# 03-CPU_Core.net
KiCad netlist of a schematic drawn in Altium Designer
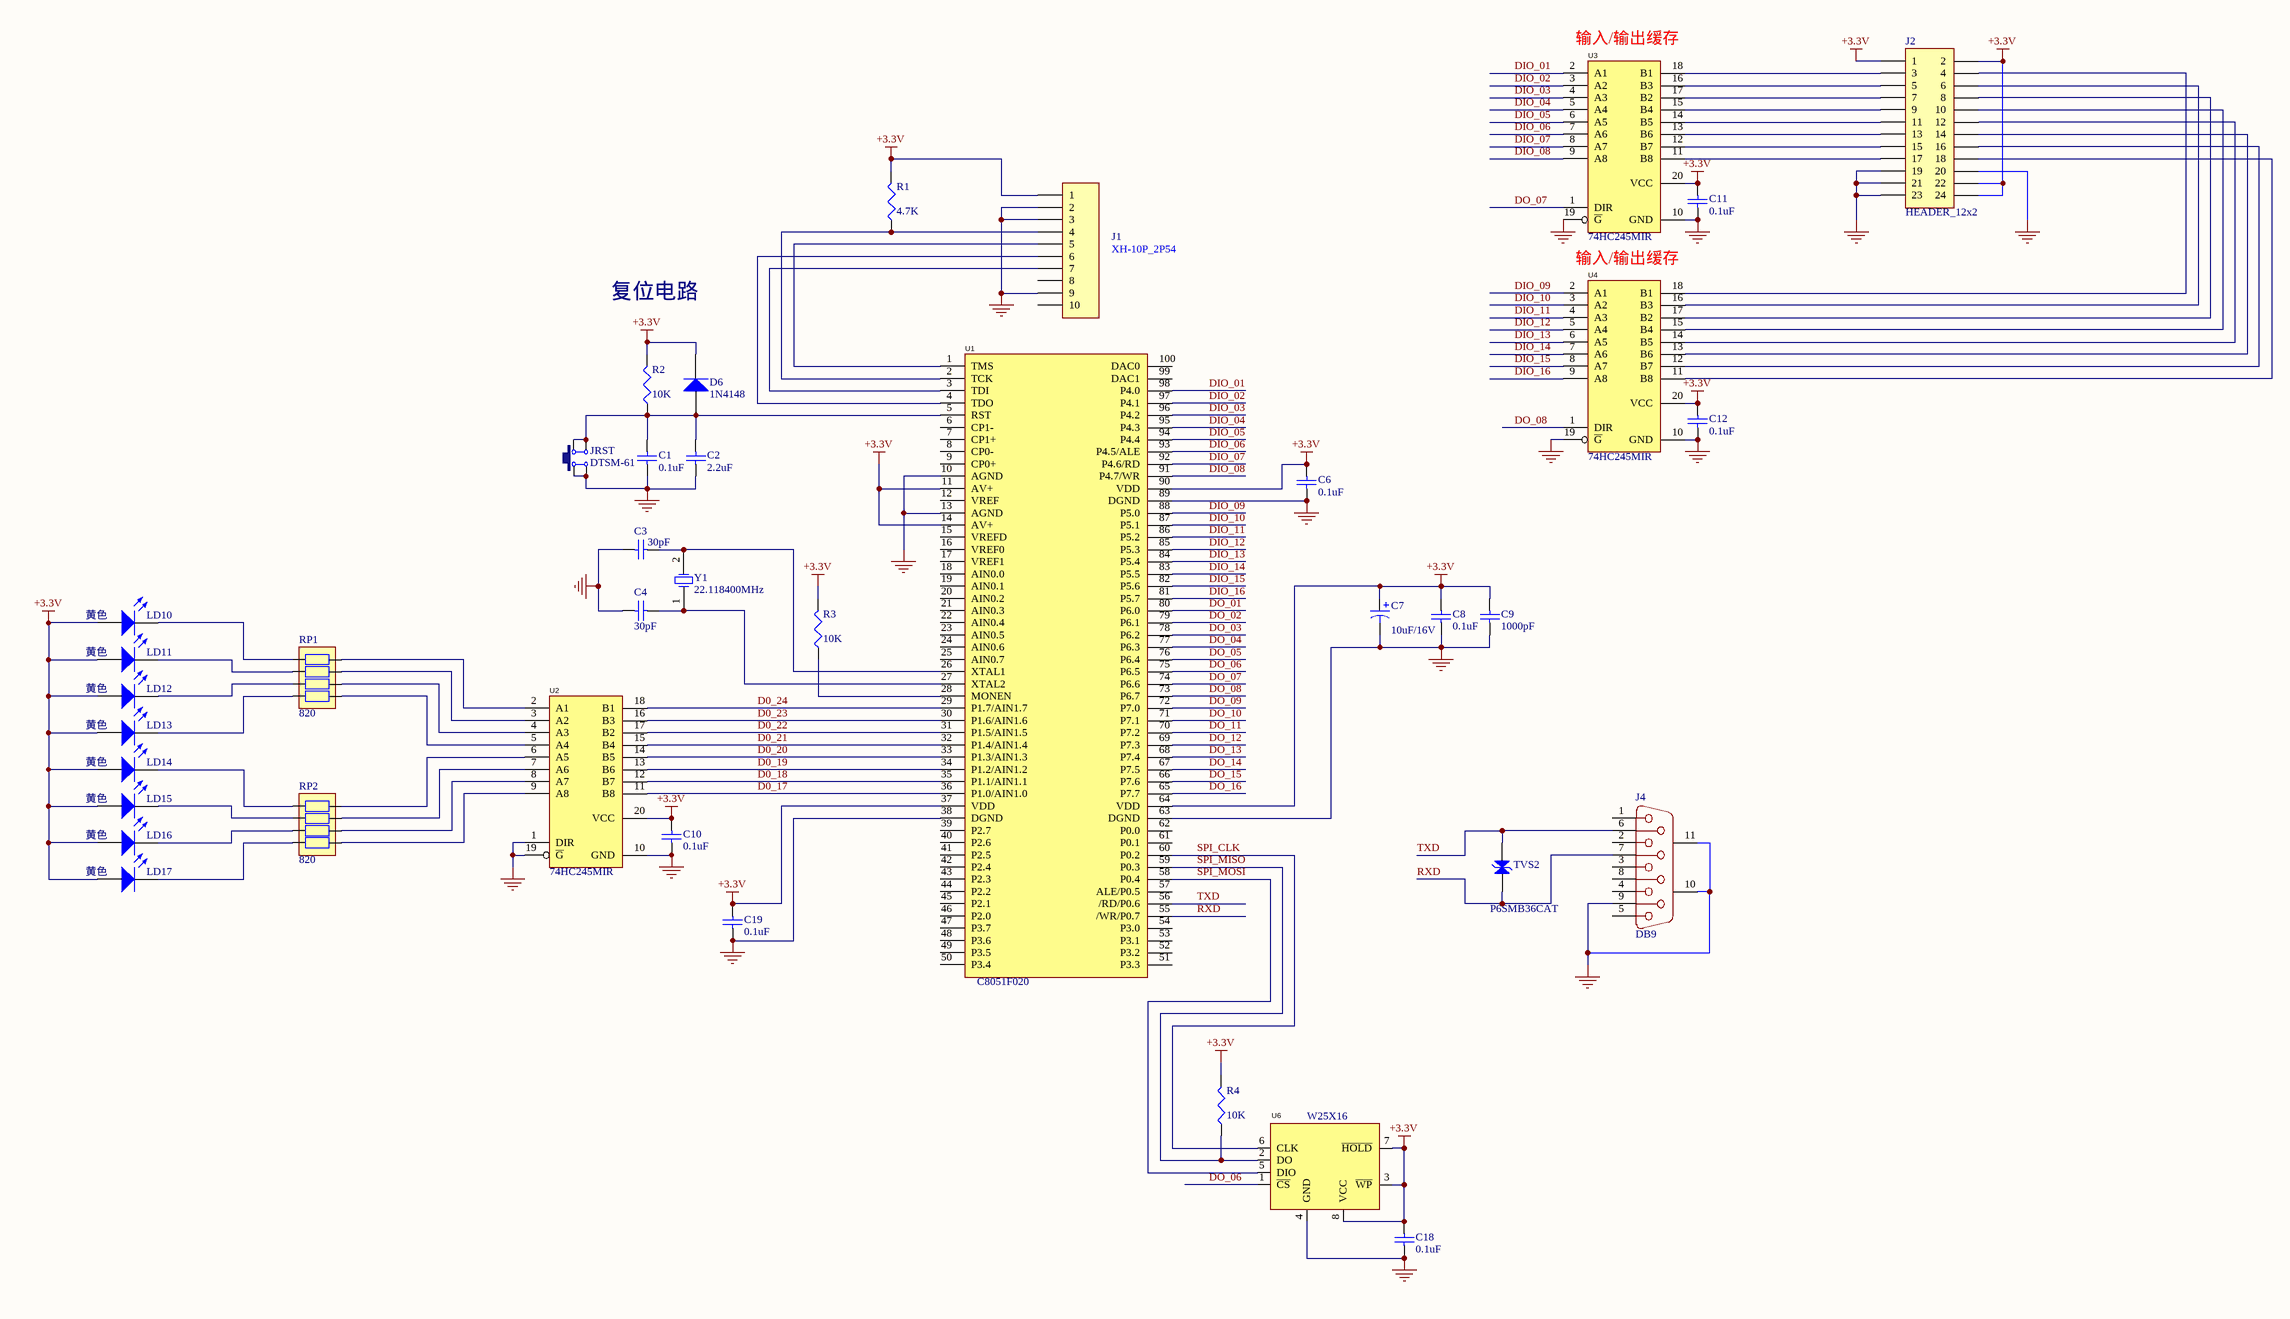
[diagram p0: 03-CPU Core.SchDoc]

(export (version "E")
  (design (tool "Eeschema 10.0.6"))
  (components
    (comp (ref "C1")
      (value "0.1uF")
      (footprint "C0805")
      (description "Capacitor")
      (fields (field (name "Comment") "Cap") (field (name "PUBLISHER") "Altium Limited"))
      (libsource (lib "Miscellaneous Devices") (part "Cap"))
    )
    (comp (ref "C2")
      (value "2.2uF")
      (footprint "C0805")
      (description "Capacitor")
      (fields (field (name "Comment") "Cap") (field (name "PUBLISHER") "Altium Limited"))
      (libsource (lib "Miscellaneous Devices") (part "Cap"))
    )
    (comp (ref "C3")
      (value "30pF")
      (footprint "C0805")
      (description "Capacitor")
      (fields (field (name "Comment") "Cap") (field (name "PUBLISHER") "Altium Limited"))
      (libsource (lib "Miscellaneous Devices") (part "Cap"))
    )
    (comp (ref "C4")
      (value "30pF")
      (footprint "C0805")
      (description "Capacitor")
      (fields (field (name "Comment") "Cap") (field (name "PUBLISHER") "Altium Limited"))
      (libsource (lib "Miscellaneous Devices") (part "Cap"))
    )
    (comp (ref "C6")
      (value "0.1uF")
      (footprint "C0805")
      (description "Capacitor")
      (fields (field (name "Comment") "Cap") (field (name "PUBLISHER") "Altium Limited"))
      (libsource (lib "Miscellaneous Devices") (part "Cap"))
    )
    (comp (ref "C7")
      (value "10uF/16V")
      (footprint "C3216")
      (description "Polarized Capacitor (Radial)")
      (fields (field (name "Comment") "Cap Pol1") (field (name "PUBLISHER") "Altium Limited"))
      (libsource (lib "Miscellaneous Devices") (part "Cap Pol1"))
    )
    (comp (ref "C8")
      (value "0.1uF")
      (footprint "C0805")
      (description "Capacitor")
      (fields (field (name "Comment") "Cap") (field (name "PUBLISHER") "Altium Limited"))
      (libsource (lib "Miscellaneous Devices") (part "Cap"))
    )
    (comp (ref "C9")
      (value "1000pF")
      (footprint "C0805")
      (description "Capacitor")
      (fields (field (name "Comment") "Cap") (field (name "PUBLISHER") "Altium Limited"))
      (libsource (lib "Miscellaneous Devices") (part "Cap"))
    )
    (comp (ref "C10")
      (value "0.1uF")
      (footprint "C0805")
      (description "Capacitor")
      (fields (field (name "Comment") "Cap") (field (name "PUBLISHER") "Altium Limited"))
      (libsource (lib "Miscellaneous Devices") (part "Cap"))
    )
    (comp (ref "C11")
      (value "0.1uF")
      (footprint "C0805")
      (description "Capacitor")
      (fields (field (name "Comment") "Cap") (field (name "PUBLISHER") "Altium Limited"))
      (libsource (lib "Miscellaneous Devices") (part "Cap"))
    )
    (comp (ref "C12")
      (value "0.1uF")
      (footprint "C0805")
      (description "Capacitor")
      (fields (field (name "Comment") "Cap") (field (name "PUBLISHER") "Altium Limited"))
      (libsource (lib "Miscellaneous Devices") (part "Cap"))
    )
    (comp (ref "C18")
      (value "0.1uF")
      (footprint "C0805")
      (description "Capacitor")
      (fields (field (name "Comment") "Cap") (field (name "PUBLISHER") "Altium Limited"))
      (libsource (lib "Miscellaneous Devices") (part "Cap"))
    )
    (comp (ref "C19")
      (value "0.1uF")
      (footprint "C0805")
      (description "Capacitor")
      (fields (field (name "Comment") "Cap") (field (name "PUBLISHER") "Altium Limited"))
      (libsource (lib "Miscellaneous Devices") (part "Cap"))
    )
    (comp (ref "D6")
      (value "1N4148")
      (footprint "FR107W")
      (description "Default Diode")
      (fields (field (name "PUBLISHER") "Altium Limited"))
      (libsource (lib "Miscellaneous Devices") (part "Diode"))
    )
    (comp (ref "J1")
      (value "XH-10P_2P54")
      (footprint "XH-10P_2P54")
      (description "Header, 10-Pin")
      (fields (field (name "PUBLISHER") "Altium Limited"))
      (libsource (lib "Miscellaneous Connectors") (part "Header 10"))
    )
    (comp (ref "J2")
      (value "HEADER_12x2")
      (footprint "HEADER_12x2")
      (description "Header, 12-Pin, Dual row")
      (fields (field (name "PUBLISHER") "Altium Limited"))
      (libsource (lib "Miscellaneous Connectors") (part "Header 12X2"))
    )
    (comp (ref "J4") (value "DB9") (footprint "DB9") (libsource (lib "SCHLIB") (part "DB9")))
    (comp (ref "JRST") (value "DTSM-61") (footprint "DISM-61") (libsource (lib "SCHLIB") (part "DTSM-61")))
    (comp (ref "LD10")
      (value "黄色")
      (footprint "LED0805")
      (description "Typical INFRARED GaAs LED")
      (fields (field (name "PUBLISHER") "Altium Limited"))
      (libsource (lib "Miscellaneous Devices") (part "LED0"))
    )
    (comp (ref "LD11")
      (value "黄色")
      (footprint "LED0805")
      (description "Typical INFRARED GaAs LED")
      (fields (field (name "PUBLISHER") "Altium Limited"))
      (libsource (lib "Miscellaneous Devices") (part "LED0"))
    )
    (comp (ref "LD12")
      (value "黄色")
      (footprint "LED0805")
      (description "Typical INFRARED GaAs LED")
      (fields (field (name "PUBLISHER") "Altium Limited"))
      (libsource (lib "Miscellaneous Devices") (part "LED0"))
    )
    (comp (ref "LD13")
      (value "黄色")
      (footprint "LED0805")
      (description "Typical INFRARED GaAs LED")
      (fields (field (name "PUBLISHER") "Altium Limited"))
      (libsource (lib "Miscellaneous Devices") (part "LED0"))
    )
    (comp (ref "LD14")
      (value "黄色")
      (footprint "LED0805")
      (description "Typical INFRARED GaAs LED")
      (fields (field (name "PUBLISHER") "Altium Limited"))
      (libsource (lib "Miscellaneous Devices") (part "LED0"))
    )
    (comp (ref "LD15")
      (value "黄色")
      (footprint "LED0805")
      (description "Typical INFRARED GaAs LED")
      (fields (field (name "PUBLISHER") "Altium Limited"))
      (libsource (lib "Miscellaneous Devices") (part "LED0"))
    )
    (comp (ref "LD16")
      (value "黄色")
      (footprint "LED0805")
      (description "Typical INFRARED GaAs LED")
      (fields (field (name "PUBLISHER") "Altium Limited"))
      (libsource (lib "Miscellaneous Devices") (part "LED0"))
    )
    (comp (ref "LD17")
      (value "黄色")
      (footprint "LED0805")
      (description "Typical INFRARED GaAs LED")
      (fields (field (name "PUBLISHER") "Altium Limited"))
      (libsource (lib "Miscellaneous Devices") (part "LED0"))
    )
    (comp (ref "R1")
      (value "4.7K")
      (footprint "R0805")
      (description "Resistor")
      (fields (field (name "Comment") "Res3") (field (name "PUBLISHER") "Altium Limited"))
      (libsource (lib "Miscellaneous Devices") (part "Res3"))
    )
    (comp (ref "R2")
      (value "10K")
      (footprint "R0805")
      (description "Resistor")
      (fields (field (name "Comment") "Res3") (field (name "PUBLISHER") "Altium Limited"))
      (libsource (lib "Miscellaneous Devices") (part "Res3"))
    )
    (comp (ref "R3")
      (value "10K")
      (footprint "R0805")
      (description "Resistor")
      (fields (field (name "Comment") "Res3") (field (name "PUBLISHER") "Altium Limited"))
      (libsource (lib "Miscellaneous Devices") (part "Res3"))
    )
    (comp (ref "R4")
      (value "10K")
      (footprint "R0805")
      (description "Resistor")
      (fields (field (name "Comment") "Res3") (field (name "PUBLISHER") "Altium Limited"))
      (libsource (lib "Miscellaneous Devices") (part "Res3"))
    )
    (comp (ref "RP1") (value "820") (footprint "RP") (libsource (lib "SCHLIB") (part "RP 820")))
    (comp (ref "RP2") (value "820") (footprint "RP") (libsource (lib "SCHLIB") (part "RP 820")))
    (comp (ref "TVS2") (value "P6SMB36CAT") (footprint "SMD") (libsource (lib "SCHLIB") (part "SMD")))
    (comp (ref "U1")
      (value "C8051F020")
      (footprint "TQFP-100")
      (fields
        (field (name "MANUFACTURER") "SKYWORKS/SILICON LABS(芯科)")
        (field (name "MANUFACTURER PART") "C8051F020-GQR")
      )
      (libsource (lib "C8051F020") (part "C8051F020"))
    )
    (comp (ref "U2")
      (value "74HC245MIR")
      (footprint "SSOP-20")
      (fields (field (name "MANUFACTURER") "Nexperia(安世)") (field (name "MANUFACTURER PART") "74HC245PW,118"))
      (libsource (lib "C8051F020") (part "74HC245MIR"))
    )
    (comp (ref "U3")
      (value "74HC245MIR")
      (footprint "SSOP-20")
      (fields (field (name "MANUFACTURER") "Nexperia(安世)") (field (name "MANUFACTURER PART") "74HC245PW,118"))
      (libsource (lib "C8051F020") (part "74HC245MIR"))
    )
    (comp (ref "U4")
      (value "74HC245MIR")
      (footprint "SSOP-20")
      (fields (field (name "MANUFACTURER") "Nexperia(安世)") (field (name "MANUFACTURER PART") "74HC245PW,118"))
      (libsource (lib "C8051F020") (part "74HC245MIR"))
    )
    (comp (ref "U6")
      (value "W25X16")
      (footprint "SOIC-8")
      (fields (field (name "MANUFACTURER") "WINBOND(华邦)") (field (name "MANUFACTURER PART") "W25X16VSSIG"))
      (libsource (lib "C8051F020") (part "W25X16"))
    )
    (comp (ref "Y1")
      (value "22.118400MHz")
      (footprint "HC-49")
      (description "Crystal Oscillator")
      (fields (field (name "PUBLISHER") "Altium Limited"))
      (libsource (lib "Miscellaneous Devices") (part "XTAL"))
    )
  )
  (nets
    (net (code "1") (name "+3.3V") (class "Default")
      (node (ref "C10") (pin "2") (pinfunction "2_2") (pintype "passive"))
      (node (ref "C11") (pin "2") (pinfunction "2_2") (pintype "passive"))
      (node (ref "C12") (pin "2") (pinfunction "2_2") (pintype "passive"))
      (node (ref "C18") (pin "2") (pinfunction "2_2") (pintype "passive"))
      (node (ref "C19") (pin "2") (pinfunction "2_2") (pintype "passive"))
      (node (ref "C6") (pin "2") (pinfunction "2_2") (pintype "passive"))
      (node (ref "C7") (pin "1") (pinfunction "1_1") (pintype "passive"))
      (node (ref "C8") (pin "2") (pinfunction "2_2") (pintype "passive"))
      (node (ref "C9") (pin "2") (pinfunction "2_2") (pintype "passive"))
      (node (ref "D6") (pin "2") (pinfunction "K_2") (pintype "passive"))
      (node (ref "J1") (pin "1") (pinfunction "1_1") (pintype "passive"))
      (node (ref "J2") (pin "1") (pinfunction "1_1") (pintype "passive"))
      (node (ref "J2") (pin "2") (pinfunction "2_2") (pintype "passive"))
      (node (ref "J2") (pin "22") (pinfunction "22_22") (pintype "passive"))
      (node (ref "J2") (pin "24") (pinfunction "24_24") (pintype "passive"))
      (node (ref "LD10") (pin "1") (pinfunction "A_1") (pintype "passive"))
      (node (ref "LD11") (pin "1") (pinfunction "A_1") (pintype "passive"))
      (node (ref "LD12") (pin "1") (pinfunction "A_1") (pintype "passive"))
      (node (ref "LD13") (pin "1") (pinfunction "A_1") (pintype "passive"))
      (node (ref "LD14") (pin "1") (pinfunction "A_1") (pintype "passive"))
      (node (ref "LD15") (pin "1") (pinfunction "A_1") (pintype "passive"))
      (node (ref "LD16") (pin "1") (pinfunction "A_1") (pintype "passive"))
      (node (ref "LD17") (pin "1") (pinfunction "A_1") (pintype "passive"))
      (node (ref "R1") (pin "2") (pinfunction "2_2") (pintype "passive"))
      (node (ref "R2") (pin "2") (pinfunction "2_2") (pintype "passive"))
      (node (ref "R3") (pin "2") (pinfunction "2_2") (pintype "passive"))
      (node (ref "R4") (pin "2") (pinfunction "2_2") (pintype "passive"))
      (node (ref "U1") (pin "11") (pinfunction "AV+_11") (pintype "passive"))
      (node (ref "U1") (pin "14") (pinfunction "AV+_14") (pintype "passive"))
      (node (ref "U1") (pin "37") (pinfunction "VDD_37") (pintype "passive"))
      (node (ref "U1") (pin "64") (pinfunction "VDD_64") (pintype "passive"))
      (node (ref "U1") (pin "90") (pinfunction "VDD_90") (pintype "passive"))
      (node (ref "U2") (pin "20") (pinfunction "VCC_20") (pintype "passive"))
      (node (ref "U3") (pin "20") (pinfunction "VCC_20") (pintype "passive"))
      (node (ref "U4") (pin "20") (pinfunction "VCC_20") (pintype "passive"))
      (node (ref "U6") (pin "3") (pinfunction "~{WP}_3") (pintype "passive"))
      (node (ref "U6") (pin "7") (pinfunction "~{HOLD}_7") (pintype "passive"))
      (node (ref "U6") (pin "8") (pinfunction "VCC_8") (pintype "passive"))
    )
    (net (code "2") (name "/D0_17") (class "Default")
      (node (ref "U1") (pin "36") (pinfunction "P1.0/AIN1.0_36") (pintype "passive"))
      (node (ref "U2") (pin "11") (pinfunction "B8_11") (pintype "passive"))
    )
    (net (code "3") (name "/D0_18") (class "Default")
      (node (ref "U1") (pin "35") (pinfunction "P1.1/AIN1.1_35") (pintype "passive"))
      (node (ref "U2") (pin "12") (pinfunction "B7_12") (pintype "passive"))
    )
    (net (code "4") (name "/D0_19") (class "Default")
      (node (ref "U1") (pin "34") (pinfunction "P1.2/AIN1.2_34") (pintype "passive"))
      (node (ref "U2") (pin "13") (pinfunction "B6_13") (pintype "passive"))
    )
    (net (code "5") (name "/D0_20") (class "Default")
      (node (ref "U1") (pin "33") (pinfunction "P1.3/AIN1.3_33") (pintype "passive"))
      (node (ref "U2") (pin "14") (pinfunction "B5_14") (pintype "passive"))
    )
    (net (code "6") (name "/D0_21") (class "Default")
      (node (ref "U1") (pin "32") (pinfunction "P1.4/AIN1.4_32") (pintype "passive"))
      (node (ref "U2") (pin "15") (pinfunction "B4_15") (pintype "passive"))
    )
    (net (code "7") (name "/D0_22") (class "Default")
      (node (ref "U1") (pin "31") (pinfunction "P1.5/AIN1.5_31") (pintype "passive"))
      (node (ref "U2") (pin "17") (pinfunction "B2_17") (pintype "passive"))
    )
    (net (code "8") (name "/D0_23") (class "Default")
      (node (ref "U1") (pin "30") (pinfunction "P1.6/AIN1.6_30") (pintype "passive"))
      (node (ref "U2") (pin "16") (pinfunction "B3_16") (pintype "passive"))
    )
    (net (code "9") (name "/D0_24") (class "Default")
      (node (ref "U1") (pin "29") (pinfunction "P1.7/AIN1.7_29") (pintype "passive"))
      (node (ref "U2") (pin "18") (pinfunction "B1_18") (pintype "passive"))
    )
    (net (code "10") (name "/DIO_01") (class "Default")
      (node (ref "U1") (pin "98") (pinfunction "P4.0_98") (pintype "passive"))
      (node (ref "U3") (pin "2") (pinfunction "A1_2") (pintype "passive"))
    )
    (net (code "11") (name "/DIO_02") (class "Default")
      (node (ref "U1") (pin "97") (pinfunction "P4.1_97") (pintype "passive"))
      (node (ref "U3") (pin "3") (pinfunction "A2_3") (pintype "passive"))
    )
    (net (code "12") (name "/DIO_03") (class "Default")
      (node (ref "U1") (pin "96") (pinfunction "P4.2_96") (pintype "passive"))
      (node (ref "U3") (pin "4") (pinfunction "A3_4") (pintype "passive"))
    )
    (net (code "13") (name "/DIO_04") (class "Default")
      (node (ref "U1") (pin "95") (pinfunction "P4.3_95") (pintype "passive"))
      (node (ref "U3") (pin "5") (pinfunction "A4_5") (pintype "passive"))
    )
    (net (code "14") (name "/DIO_05") (class "Default")
      (node (ref "U1") (pin "94") (pinfunction "P4.4_94") (pintype "passive"))
      (node (ref "U3") (pin "6") (pinfunction "A5_6") (pintype "passive"))
    )
    (net (code "15") (name "/DIO_06") (class "Default")
      (node (ref "U1") (pin "93") (pinfunction "P4.5/ALE_93") (pintype "passive"))
      (node (ref "U3") (pin "7") (pinfunction "A6_7") (pintype "passive"))
    )
    (net (code "16") (name "/DIO_07") (class "Default")
      (node (ref "U1") (pin "92") (pinfunction "P4.6/RD_92") (pintype "passive"))
      (node (ref "U3") (pin "8") (pinfunction "A7_8") (pintype "passive"))
    )
    (net (code "17") (name "/DIO_08") (class "Default")
      (node (ref "U1") (pin "91") (pinfunction "P4.7/WR_91") (pintype "passive"))
      (node (ref "U3") (pin "9") (pinfunction "A8_9") (pintype "passive"))
    )
    (net (code "18") (name "/DIO_09") (class "Default")
      (node (ref "U1") (pin "88") (pinfunction "P5.0_88") (pintype "passive"))
      (node (ref "U4") (pin "2") (pinfunction "A1_2") (pintype "passive"))
    )
    (net (code "19") (name "/DIO_10") (class "Default")
      (node (ref "U1") (pin "87") (pinfunction "P5.1_87") (pintype "passive"))
      (node (ref "U4") (pin "3") (pinfunction "A2_3") (pintype "passive"))
    )
    (net (code "20") (name "/DIO_11") (class "Default")
      (node (ref "U1") (pin "86") (pinfunction "P5.2_86") (pintype "passive"))
      (node (ref "U4") (pin "4") (pinfunction "A3_4") (pintype "passive"))
    )
    (net (code "21") (name "/DIO_12") (class "Default")
      (node (ref "U1") (pin "85") (pinfunction "P5.3_85") (pintype "passive"))
      (node (ref "U4") (pin "5") (pinfunction "A4_5") (pintype "passive"))
    )
    (net (code "22") (name "/DIO_13") (class "Default")
      (node (ref "U1") (pin "84") (pinfunction "P5.4_84") (pintype "passive"))
      (node (ref "U4") (pin "6") (pinfunction "A5_6") (pintype "passive"))
    )
    (net (code "23") (name "/DIO_14") (class "Default")
      (node (ref "U1") (pin "83") (pinfunction "P5.5_83") (pintype "passive"))
      (node (ref "U4") (pin "7") (pinfunction "A6_7") (pintype "passive"))
    )
    (net (code "24") (name "/DIO_15") (class "Default")
      (node (ref "U1") (pin "82") (pinfunction "P5.6_82") (pintype "passive"))
      (node (ref "U4") (pin "8") (pinfunction "A7_8") (pintype "passive"))
    )
    (net (code "25") (name "/DIO_16") (class "Default")
      (node (ref "U1") (pin "81") (pinfunction "P5.7_81") (pintype "passive"))
      (node (ref "U4") (pin "9") (pinfunction "A8_9") (pintype "passive"))
    )
    (net (code "26") (name "/DO_01") (class "Default")
      (node (ref "U1") (pin "80") (pinfunction "P6.0_80") (pintype "passive"))
    )
    (net (code "27") (name "/DO_02") (class "Default")
      (node (ref "U1") (pin "79") (pinfunction "P6.1_79") (pintype "passive"))
    )
    (net (code "28") (name "/DO_03") (class "Default")
      (node (ref "U1") (pin "78") (pinfunction "P6.2_78") (pintype "passive"))
    )
    (net (code "29") (name "/DO_04") (class "Default")
      (node (ref "U1") (pin "77") (pinfunction "P6.3_77") (pintype "passive"))
    )
    (net (code "30") (name "/DO_05") (class "Default")
      (node (ref "U1") (pin "76") (pinfunction "P6.4_76") (pintype "passive"))
    )
    (net (code "31") (name "/DO_06") (class "Default")
      (node (ref "U1") (pin "75") (pinfunction "P6.5_75") (pintype "passive"))
      (node (ref "U6") (pin "1") (pinfunction "~{CS}_1") (pintype "passive"))
    )
    (net (code "32") (name "/DO_07") (class "Default")
      (node (ref "U1") (pin "74") (pinfunction "P6.6_74") (pintype "passive"))
      (node (ref "U3") (pin "1") (pinfunction "DIR_1") (pintype "passive"))
    )
    (net (code "33") (name "/DO_08") (class "Default")
      (node (ref "U1") (pin "73") (pinfunction "P6.7_73") (pintype "passive"))
      (node (ref "U4") (pin "1") (pinfunction "DIR_1") (pintype "passive"))
    )
    (net (code "34") (name "/DO_09") (class "Default")
      (node (ref "U1") (pin "72") (pinfunction "P7.0_72") (pintype "passive"))
    )
    (net (code "35") (name "/DO_10") (class "Default")
      (node (ref "U1") (pin "71") (pinfunction "P7.1_71") (pintype "passive"))
    )
    (net (code "36") (name "/DO_11") (class "Default")
      (node (ref "U1") (pin "70") (pinfunction "P7.2_70") (pintype "passive"))
    )
    (net (code "37") (name "/DO_12") (class "Default")
      (node (ref "U1") (pin "69") (pinfunction "P7.3_69") (pintype "passive"))
    )
    (net (code "38") (name "/DO_13") (class "Default")
      (node (ref "U1") (pin "68") (pinfunction "P7.4_68") (pintype "passive"))
    )
    (net (code "39") (name "/DO_14") (class "Default")
      (node (ref "U1") (pin "67") (pinfunction "P7.5_67") (pintype "passive"))
    )
    (net (code "40") (name "/DO_15") (class "Default")
      (node (ref "U1") (pin "66") (pinfunction "P7.6_66") (pintype "passive"))
    )
    (net (code "41") (name "/DO_16") (class "Default")
      (node (ref "U1") (pin "65") (pinfunction "P7.7_65") (pintype "passive"))
    )
    (net (code "42") (name "/RXD") (class "Default")
      (node (ref "J4") (pin "7") (pinfunction "7_7") (pintype "passive"))
      (node (ref "TVS2") (pin "2") (pinfunction "K_2") (pintype "passive"))
      (node (ref "U1") (pin "55") (pinfunction "/WR/P0.7_55") (pintype "passive"))
    )
    (net (code "43") (name "/SPI_CLK") (class "Default")
      (node (ref "U1") (pin "60") (pinfunction "P0.2_60") (pintype "passive"))
      (node (ref "U6") (pin "6") (pinfunction "CLK_6") (pintype "passive"))
    )
    (net (code "44") (name "/SPI_MISO") (class "Default")
      (node (ref "R4") (pin "1") (pinfunction "1_1") (pintype "passive"))
      (node (ref "U1") (pin "59") (pinfunction "P0.3_59") (pintype "passive"))
      (node (ref "U6") (pin "2") (pinfunction "DO_2") (pintype "passive"))
    )
    (net (code "45") (name "/SPI_MOSI") (class "Default")
      (node (ref "U1") (pin "58") (pinfunction "P0.4_58") (pintype "passive"))
      (node (ref "U6") (pin "5") (pinfunction "DIO_5") (pintype "passive"))
    )
    (net (code "46") (name "/TXD") (class "Default")
      (node (ref "J4") (pin "6") (pinfunction "6_6") (pintype "passive"))
      (node (ref "TVS2") (pin "1") (pinfunction "A_1") (pintype "passive"))
      (node (ref "U1") (pin "56") (pinfunction "/RD/P0.6_56") (pintype "passive"))
    )
    (net (code "47") (name "GND") (class "Default")
      (node (ref "C1") (pin "2") (pinfunction "2_2") (pintype "passive"))
      (node (ref "C10") (pin "1") (pinfunction "1_1") (pintype "passive"))
      (node (ref "C11") (pin "1") (pinfunction "1_1") (pintype "passive"))
      (node (ref "C12") (pin "1") (pinfunction "1_1") (pintype "passive"))
      (node (ref "C18") (pin "1") (pinfunction "1_1") (pintype "passive"))
      (node (ref "C19") (pin "1") (pinfunction "1_1") (pintype "passive"))
      (node (ref "C2") (pin "2") (pinfunction "2_2") (pintype "passive"))
      (node (ref "C3") (pin "1") (pinfunction "1_1") (pintype "passive"))
      (node (ref "C4") (pin "1") (pinfunction "1_1") (pintype "passive"))
      (node (ref "C6") (pin "1") (pinfunction "1_1") (pintype "passive"))
      (node (ref "C7") (pin "2") (pinfunction "2_2") (pintype "passive"))
      (node (ref "C8") (pin "1") (pinfunction "1_1") (pintype "passive"))
      (node (ref "C9") (pin "1") (pinfunction "1_1") (pintype "passive"))
      (node (ref "J1") (pin "2") (pinfunction "2_2") (pintype "passive"))
      (node (ref "J1") (pin "3") (pinfunction "3_3") (pintype "passive"))
      (node (ref "J1") (pin "9") (pinfunction "9_9") (pintype "passive"))
      (node (ref "J2") (pin "19") (pinfunction "19_19") (pintype "passive"))
      (node (ref "J2") (pin "20") (pinfunction "20_20") (pintype "passive"))
      (node (ref "J2") (pin "21") (pinfunction "21_21") (pintype "passive"))
      (node (ref "J2") (pin "23") (pinfunction "23_23") (pintype "passive"))
      (node (ref "J4") (pin "10") (pinfunction "MH1_10") (pintype "passive"))
      (node (ref "J4") (pin "11") (pinfunction "MH2_11") (pintype "passive"))
      (node (ref "J4") (pin "9") (pinfunction "9_9") (pintype "passive"))
      (node (ref "JRST") (pin "1") (pinfunction "1_1") (pintype "passive"))
      (node (ref "JRST") (pin "4") (pinfunction "4_4") (pintype "passive"))
      (node (ref "U1") (pin "10") (pinfunction "AGND_10") (pintype "passive"))
      (node (ref "U1") (pin "13") (pinfunction "AGND_13") (pintype "passive"))
      (node (ref "U1") (pin "38") (pinfunction "DGND_38") (pintype "passive"))
      (node (ref "U1") (pin "63") (pinfunction "DGND_63") (pintype "passive"))
      (node (ref "U1") (pin "89") (pinfunction "DGND_89") (pintype "passive"))
      (node (ref "U2") (pin "1") (pinfunction "DIR_1") (pintype "passive"))
      (node (ref "U2") (pin "10") (pinfunction "GND_10") (pintype "passive"))
      (node (ref "U2") (pin "19") (pinfunction "~{G}_19") (pintype "passive"))
      (node (ref "U3") (pin "10") (pinfunction "GND_10") (pintype "passive"))
      (node (ref "U3") (pin "19") (pinfunction "~{G}_19") (pintype "passive"))
      (node (ref "U4") (pin "10") (pinfunction "GND_10") (pintype "passive"))
      (node (ref "U4") (pin "19") (pinfunction "~{G}_19") (pintype "passive"))
      (node (ref "U6") (pin "4") (pinfunction "GND_4") (pintype "passive"))
    )
    (net (code "48") (name "Net-(D6-A)") (class "Default")
      (node (ref "C1") (pin "1") (pinfunction "1_1") (pintype "passive"))
      (node (ref "C2") (pin "1") (pinfunction "1_1") (pintype "passive"))
      (node (ref "D6") (pin "1") (pinfunction "A_1") (pintype "passive"))
      (node (ref "JRST") (pin "2") (pinfunction "2_2") (pintype "passive"))
      (node (ref "JRST") (pin "3") (pinfunction "3_3") (pintype "passive"))
      (node (ref "R2") (pin "1") (pinfunction "1_1") (pintype "passive"))
      (node (ref "U1") (pin "5") (pinfunction "RST_5") (pintype "passive"))
    )
    (net (code "49") (name "Net-(LD10-K)") (class "Default")
      (node (ref "LD10") (pin "2") (pinfunction "K_2") (pintype "passive"))
      (node (ref "RP1") (pin "1") (pinfunction "1_1") (pintype "passive"))
    )
    (net (code "50") (name "Net-(LD11-K)") (class "Default")
      (node (ref "LD11") (pin "2") (pinfunction "K_2") (pintype "passive"))
      (node (ref "RP1") (pin "2") (pinfunction "2_2") (pintype "passive"))
    )
    (net (code "51") (name "Net-(LD12-K)") (class "Default")
      (node (ref "LD12") (pin "2") (pinfunction "K_2") (pintype "passive"))
      (node (ref "RP1") (pin "3") (pinfunction "3_3") (pintype "passive"))
    )
    (net (code "52") (name "Net-(LD13-K)") (class "Default")
      (node (ref "LD13") (pin "2") (pinfunction "K_2") (pintype "passive"))
      (node (ref "RP1") (pin "4") (pinfunction "4_4") (pintype "passive"))
    )
    (net (code "53") (name "Net-(LD14-K)") (class "Default")
      (node (ref "LD14") (pin "2") (pinfunction "K_2") (pintype "passive"))
      (node (ref "RP2") (pin "1") (pinfunction "1_1") (pintype "passive"))
    )
    (net (code "54") (name "Net-(LD15-K)") (class "Default")
      (node (ref "LD15") (pin "2") (pinfunction "K_2") (pintype "passive"))
      (node (ref "RP2") (pin "2") (pinfunction "2_2") (pintype "passive"))
    )
    (net (code "55") (name "Net-(LD16-K)") (class "Default")
      (node (ref "LD16") (pin "2") (pinfunction "K_2") (pintype "passive"))
      (node (ref "RP2") (pin "3") (pinfunction "3_3") (pintype "passive"))
    )
    (net (code "56") (name "Net-(LD17-K)") (class "Default")
      (node (ref "LD17") (pin "2") (pinfunction "K_2") (pintype "passive"))
      (node (ref "RP2") (pin "4") (pinfunction "4_4") (pintype "passive"))
    )
    (net (code "57") (name "Net-(U1-MONEN)") (class "Default")
      (node (ref "R3") (pin "1") (pinfunction "1_1") (pintype "passive"))
      (node (ref "U1") (pin "28") (pinfunction "MONEN_28") (pintype "passive"))
    )
    (net (code "58") (name "Net-(U1-TCK)") (class "Default")
      (node (ref "J1") (pin "4") (pinfunction "4_4") (pintype "passive"))
      (node (ref "R1") (pin "1") (pinfunction "1_1") (pintype "passive"))
      (node (ref "U1") (pin "2") (pinfunction "TCK_2") (pintype "passive"))
    )
    (net (code "59") (name "Net-(U1-TDI)") (class "Default")
      (node (ref "J1") (pin "7") (pinfunction "7_7") (pintype "passive"))
      (node (ref "U1") (pin "3") (pinfunction "TDI_3") (pintype "passive"))
    )
    (net (code "60") (name "Net-(U1-TDO)") (class "Default")
      (node (ref "J1") (pin "6") (pinfunction "6_6") (pintype "passive"))
      (node (ref "U1") (pin "4") (pinfunction "TDO_4") (pintype "passive"))
    )
    (net (code "61") (name "Net-(U1-TMS)") (class "Default")
      (node (ref "J1") (pin "5") (pinfunction "5_5") (pintype "passive"))
      (node (ref "U1") (pin "1") (pinfunction "TMS_1") (pintype "passive"))
    )
    (net (code "62") (name "Net-(U1-XTAL1)") (class "Default")
      (node (ref "C3") (pin "2") (pinfunction "2_2") (pintype "passive"))
      (node (ref "U1") (pin "26") (pinfunction "XTAL1_26") (pintype "passive"))
      (node (ref "Y1") (pin "2") (pinfunction "OSC2_2") (pintype "passive"))
    )
    (net (code "63") (name "Net-(U1-XTAL2)") (class "Default")
      (node (ref "C4") (pin "2") (pinfunction "2_2") (pintype "passive"))
      (node (ref "U1") (pin "27") (pinfunction "XTAL2_27") (pintype "passive"))
      (node (ref "Y1") (pin "1") (pinfunction "OSC1_1") (pintype "passive"))
    )
    (net (code "64") (name "Net-(U2-A1)") (class "Default")
      (node (ref "RP1") (pin "8") (pinfunction "8_8") (pintype "passive"))
      (node (ref "U2") (pin "2") (pinfunction "A1_2") (pintype "passive"))
    )
    (net (code "65") (name "Net-(U2-A2)") (class "Default")
      (node (ref "RP1") (pin "7") (pinfunction "7_7") (pintype "passive"))
      (node (ref "U2") (pin "3") (pinfunction "A2_3") (pintype "passive"))
    )
    (net (code "66") (name "Net-(U2-A3)") (class "Default")
      (node (ref "RP1") (pin "6") (pinfunction "6_6") (pintype "passive"))
      (node (ref "U2") (pin "4") (pinfunction "A3_4") (pintype "passive"))
    )
    (net (code "67") (name "Net-(U2-A4)") (class "Default")
      (node (ref "RP1") (pin "5") (pinfunction "5_5") (pintype "passive"))
      (node (ref "U2") (pin "5") (pinfunction "A4_5") (pintype "passive"))
    )
    (net (code "68") (name "Net-(U2-A5)") (class "Default")
      (node (ref "RP2") (pin "8") (pinfunction "8_8") (pintype "passive"))
      (node (ref "U2") (pin "6") (pinfunction "A5_6") (pintype "passive"))
    )
    (net (code "69") (name "Net-(U2-A6)") (class "Default")
      (node (ref "RP2") (pin "7") (pinfunction "7_7") (pintype "passive"))
      (node (ref "U2") (pin "7") (pinfunction "A6_7") (pintype "passive"))
    )
    (net (code "70") (name "Net-(U2-A7)") (class "Default")
      (node (ref "RP2") (pin "6") (pinfunction "6_6") (pintype "passive"))
      (node (ref "U2") (pin "8") (pinfunction "A7_8") (pintype "passive"))
    )
    (net (code "71") (name "Net-(U2-A8)") (class "Default")
      (node (ref "RP2") (pin "5") (pinfunction "5_5") (pintype "passive"))
      (node (ref "U2") (pin "9") (pinfunction "A8_9") (pintype "passive"))
    )
    (net (code "72") (name "Net-(U3-B1)") (class "Default")
      (node (ref "J2") (pin "3") (pinfunction "3_3") (pintype "passive"))
      (node (ref "U3") (pin "18") (pinfunction "B1_18") (pintype "passive"))
    )
    (net (code "73") (name "Net-(U3-B2)") (class "Default")
      (node (ref "J2") (pin "7") (pinfunction "7_7") (pintype "passive"))
      (node (ref "U3") (pin "17") (pinfunction "B2_17") (pintype "passive"))
    )
    (net (code "74") (name "Net-(U3-B3)") (class "Default")
      (node (ref "J2") (pin "5") (pinfunction "5_5") (pintype "passive"))
      (node (ref "U3") (pin "16") (pinfunction "B3_16") (pintype "passive"))
    )
    (net (code "75") (name "Net-(U3-B4)") (class "Default")
      (node (ref "J2") (pin "9") (pinfunction "9_9") (pintype "passive"))
      (node (ref "U3") (pin "15") (pinfunction "B4_15") (pintype "passive"))
    )
    (net (code "76") (name "Net-(U3-B5)") (class "Default")
      (node (ref "J2") (pin "11") (pinfunction "11_11") (pintype "passive"))
      (node (ref "U3") (pin "14") (pinfunction "B5_14") (pintype "passive"))
    )
    (net (code "77") (name "Net-(U3-B6)") (class "Default")
      (node (ref "J2") (pin "13") (pinfunction "13_13") (pintype "passive"))
      (node (ref "U3") (pin "13") (pinfunction "B6_13") (pintype "passive"))
    )
    (net (code "78") (name "Net-(U3-B7)") (class "Default")
      (node (ref "J2") (pin "15") (pinfunction "15_15") (pintype "passive"))
      (node (ref "U3") (pin "12") (pinfunction "B7_12") (pintype "passive"))
    )
    (net (code "79") (name "Net-(U3-B8)") (class "Default")
      (node (ref "J2") (pin "17") (pinfunction "17_17") (pintype "passive"))
      (node (ref "U3") (pin "11") (pinfunction "B8_11") (pintype "passive"))
    )
    (net (code "80") (name "Net-(U4-B1)") (class "Default")
      (node (ref "J2") (pin "4") (pinfunction "4_4") (pintype "passive"))
      (node (ref "U4") (pin "18") (pinfunction "B1_18") (pintype "passive"))
    )
    (net (code "81") (name "Net-(U4-B2)") (class "Default")
      (node (ref "J2") (pin "8") (pinfunction "8_8") (pintype "passive"))
      (node (ref "U4") (pin "17") (pinfunction "B2_17") (pintype "passive"))
    )
    (net (code "82") (name "Net-(U4-B3)") (class "Default")
      (node (ref "J2") (pin "6") (pinfunction "6_6") (pintype "passive"))
      (node (ref "U4") (pin "16") (pinfunction "B3_16") (pintype "passive"))
    )
    (net (code "83") (name "Net-(U4-B4)") (class "Default")
      (node (ref "J2") (pin "10") (pinfunction "10_10") (pintype "passive"))
      (node (ref "U4") (pin "15") (pinfunction "B4_15") (pintype "passive"))
    )
    (net (code "84") (name "Net-(U4-B5)") (class "Default")
      (node (ref "J2") (pin "12") (pinfunction "12_12") (pintype "passive"))
      (node (ref "U4") (pin "14") (pinfunction "B5_14") (pintype "passive"))
    )
    (net (code "85") (name "Net-(U4-B6)") (class "Default")
      (node (ref "J2") (pin "14") (pinfunction "14_14") (pintype "passive"))
      (node (ref "U4") (pin "13") (pinfunction "B6_13") (pintype "passive"))
    )
    (net (code "86") (name "Net-(U4-B7)") (class "Default")
      (node (ref "J2") (pin "16") (pinfunction "16_16") (pintype "passive"))
      (node (ref "U4") (pin "12") (pinfunction "B7_12") (pintype "passive"))
    )
    (net (code "87") (name "Net-(U4-B8)") (class "Default")
      (node (ref "J2") (pin "18") (pinfunction "18_18") (pintype "passive"))
      (node (ref "U4") (pin "11") (pinfunction "B8_11") (pintype "passive"))
    )
    (net (code "88") (name "unconnected-(J1-Pad8)") (class "Default")
      (node (ref "J1") (pin "8") (pinfunction "8_8") (pintype "passive"))
    )
    (net (code "89") (name "unconnected-(J1-Pad10)") (class "Default")
      (node (ref "J1") (pin "10") (pinfunction "10_10") (pintype "passive"))
    )
    (net (code "90") (name "unconnected-(J4-Pad1)") (class "Default")
      (node (ref "J4") (pin "1") (pinfunction "1_1") (pintype "passive"))
    )
    (net (code "91") (name "unconnected-(J4-Pad2)") (class "Default")
      (node (ref "J4") (pin "2") (pinfunction "2_2") (pintype "passive"))
    )
    (net (code "92") (name "unconnected-(J4-Pad3)") (class "Default")
      (node (ref "J4") (pin "3") (pinfunction "3_3") (pintype "passive"))
    )
    (net (code "93") (name "unconnected-(J4-Pad4)") (class "Default")
      (node (ref "J4") (pin "4") (pinfunction "4_4") (pintype "passive"))
    )
    (net (code "94") (name "unconnected-(J4-Pad5)") (class "Default")
      (node (ref "J4") (pin "5") (pinfunction "5_5") (pintype "passive"))
    )
    (net (code "95") (name "unconnected-(J4-Pad8)") (class "Default")
      (node (ref "J4") (pin "8") (pinfunction "8_8") (pintype "passive"))
    )
    (net (code "96") (name "unconnected-(U1-AIN0.0-Pad18)") (class "Default")
      (node (ref "U1") (pin "18") (pinfunction "AIN0.0_18") (pintype "passive"))
    )
    (net (code "97") (name "unconnected-(U1-AIN0.1-Pad19)") (class "Default")
      (node (ref "U1") (pin "19") (pinfunction "AIN0.1_19") (pintype "passive"))
    )
    (net (code "98") (name "unconnected-(U1-AIN0.2-Pad20)") (class "Default")
      (node (ref "U1") (pin "20") (pinfunction "AIN0.2_20") (pintype "passive"))
    )
    (net (code "99") (name "unconnected-(U1-AIN0.3-Pad21)") (class "Default")
      (node (ref "U1") (pin "21") (pinfunction "AIN0.3_21") (pintype "passive"))
    )
    (net (code "100") (name "unconnected-(U1-AIN0.4-Pad22)") (class "Default")
      (node (ref "U1") (pin "22") (pinfunction "AIN0.4_22") (pintype "passive"))
    )
    (net (code "101") (name "unconnected-(U1-AIN0.5-Pad23)") (class "Default")
      (node (ref "U1") (pin "23") (pinfunction "AIN0.5_23") (pintype "passive"))
    )
    (net (code "102") (name "unconnected-(U1-AIN0.6-Pad24)") (class "Default")
      (node (ref "U1") (pin "24") (pinfunction "AIN0.6_24") (pintype "passive"))
    )
    (net (code "103") (name "unconnected-(U1-AIN0.7-Pad25)") (class "Default")
      (node (ref "U1") (pin "25") (pinfunction "AIN0.7_25") (pintype "passive"))
    )
    (net (code "104") (name "unconnected-(U1-ALE{slash}P0.5-Pad57)") (class "Default")
      (node (ref "U1") (pin "57") (pinfunction "ALE/P0.5_57") (pintype "passive"))
    )
    (net (code "105") (name "unconnected-(U1-CP0+-Pad9)") (class "Default")
      (node (ref "U1") (pin "9") (pinfunction "CP0+_9") (pintype "passive"))
    )
    (net (code "106") (name "unconnected-(U1-CP0--Pad8)") (class "Default")
      (node (ref "U1") (pin "8") (pinfunction "CP0-_8") (pintype "passive"))
    )
    (net (code "107") (name "unconnected-(U1-CP1+-Pad7)") (class "Default")
      (node (ref "U1") (pin "7") (pinfunction "CP1+_7") (pintype "passive"))
    )
    (net (code "108") (name "unconnected-(U1-CP1--Pad6)") (class "Default")
      (node (ref "U1") (pin "6") (pinfunction "CP1-_6") (pintype "passive"))
    )
    (net (code "109") (name "unconnected-(U1-DAC0-Pad100)") (class "Default")
      (node (ref "U1") (pin "100") (pinfunction "DAC0_100") (pintype "passive"))
    )
    (net (code "110") (name "unconnected-(U1-DAC1-Pad99)") (class "Default")
      (node (ref "U1") (pin "99") (pinfunction "DAC1_99") (pintype "passive"))
    )
    (net (code "111") (name "unconnected-(U1-P0.0-Pad62)") (class "Default")
      (node (ref "U1") (pin "62") (pinfunction "P0.0_62") (pintype "passive"))
    )
    (net (code "112") (name "unconnected-(U1-P0.1-Pad61)") (class "Default")
      (node (ref "U1") (pin "61") (pinfunction "P0.1_61") (pintype "passive"))
    )
    (net (code "113") (name "unconnected-(U1-P2.0-Pad46)") (class "Default")
      (node (ref "U1") (pin "46") (pinfunction "P2.0_46") (pintype "passive"))
    )
    (net (code "114") (name "unconnected-(U1-P2.1-Pad45)") (class "Default")
      (node (ref "U1") (pin "45") (pinfunction "P2.1_45") (pintype "passive"))
    )
    (net (code "115") (name "unconnected-(U1-P2.2-Pad44)") (class "Default")
      (node (ref "U1") (pin "44") (pinfunction "P2.2_44") (pintype "passive"))
    )
    (net (code "116") (name "unconnected-(U1-P2.3-Pad43)") (class "Default")
      (node (ref "U1") (pin "43") (pinfunction "P2.3_43") (pintype "passive"))
    )
    (net (code "117") (name "unconnected-(U1-P2.4-Pad42)") (class "Default")
      (node (ref "U1") (pin "42") (pinfunction "P2.4_42") (pintype "passive"))
    )
    (net (code "118") (name "unconnected-(U1-P2.5-Pad41)") (class "Default")
      (node (ref "U1") (pin "41") (pinfunction "P2.5_41") (pintype "passive"))
    )
    (net (code "119") (name "unconnected-(U1-P2.6-Pad40)") (class "Default")
      (node (ref "U1") (pin "40") (pinfunction "P2.6_40") (pintype "passive"))
    )
    (net (code "120") (name "unconnected-(U1-P2.7-Pad39)") (class "Default")
      (node (ref "U1") (pin "39") (pinfunction "P2.7_39") (pintype "passive"))
    )
    (net (code "121") (name "unconnected-(U1-P3.0-Pad54)") (class "Default")
      (node (ref "U1") (pin "54") (pinfunction "P3.0_54") (pintype "passive"))
    )
    (net (code "122") (name "unconnected-(U1-P3.1-Pad53)") (class "Default")
      (node (ref "U1") (pin "53") (pinfunction "P3.1_53") (pintype "passive"))
    )
    (net (code "123") (name "unconnected-(U1-P3.2-Pad52)") (class "Default")
      (node (ref "U1") (pin "52") (pinfunction "P3.2_52") (pintype "passive"))
    )
    (net (code "124") (name "unconnected-(U1-P3.3-Pad51)") (class "Default")
      (node (ref "U1") (pin "51") (pinfunction "P3.3_51") (pintype "passive"))
    )
    (net (code "125") (name "unconnected-(U1-P3.4-Pad50)") (class "Default")
      (node (ref "U1") (pin "50") (pinfunction "P3.4_50") (pintype "passive"))
    )
    (net (code "126") (name "unconnected-(U1-P3.5-Pad49)") (class "Default")
      (node (ref "U1") (pin "49") (pinfunction "P3.5_49") (pintype "passive"))
    )
    (net (code "127") (name "unconnected-(U1-P3.6-Pad48)") (class "Default")
      (node (ref "U1") (pin "48") (pinfunction "P3.6_48") (pintype "passive"))
    )
    (net (code "128") (name "unconnected-(U1-P3.7-Pad47)") (class "Default")
      (node (ref "U1") (pin "47") (pinfunction "P3.7_47") (pintype "passive"))
    )
    (net (code "129") (name "unconnected-(U1-VREF-Pad12)") (class "Default")
      (node (ref "U1") (pin "12") (pinfunction "VREF_12") (pintype "passive"))
    )
    (net (code "130") (name "unconnected-(U1-VREF0-Pad16)") (class "Default")
      (node (ref "U1") (pin "16") (pinfunction "VREF0_16") (pintype "passive"))
    )
    (net (code "131") (name "unconnected-(U1-VREF1-Pad17)") (class "Default")
      (node (ref "U1") (pin "17") (pinfunction "VREF1_17") (pintype "passive"))
    )
    (net (code "132") (name "unconnected-(U1-VREFD-Pad15)") (class "Default")
      (node (ref "U1") (pin "15") (pinfunction "VREFD_15") (pintype "passive"))
    )
  )
)
